# SheetSensor.net
KiCad netlist of a schematic drawn in Altium Designer
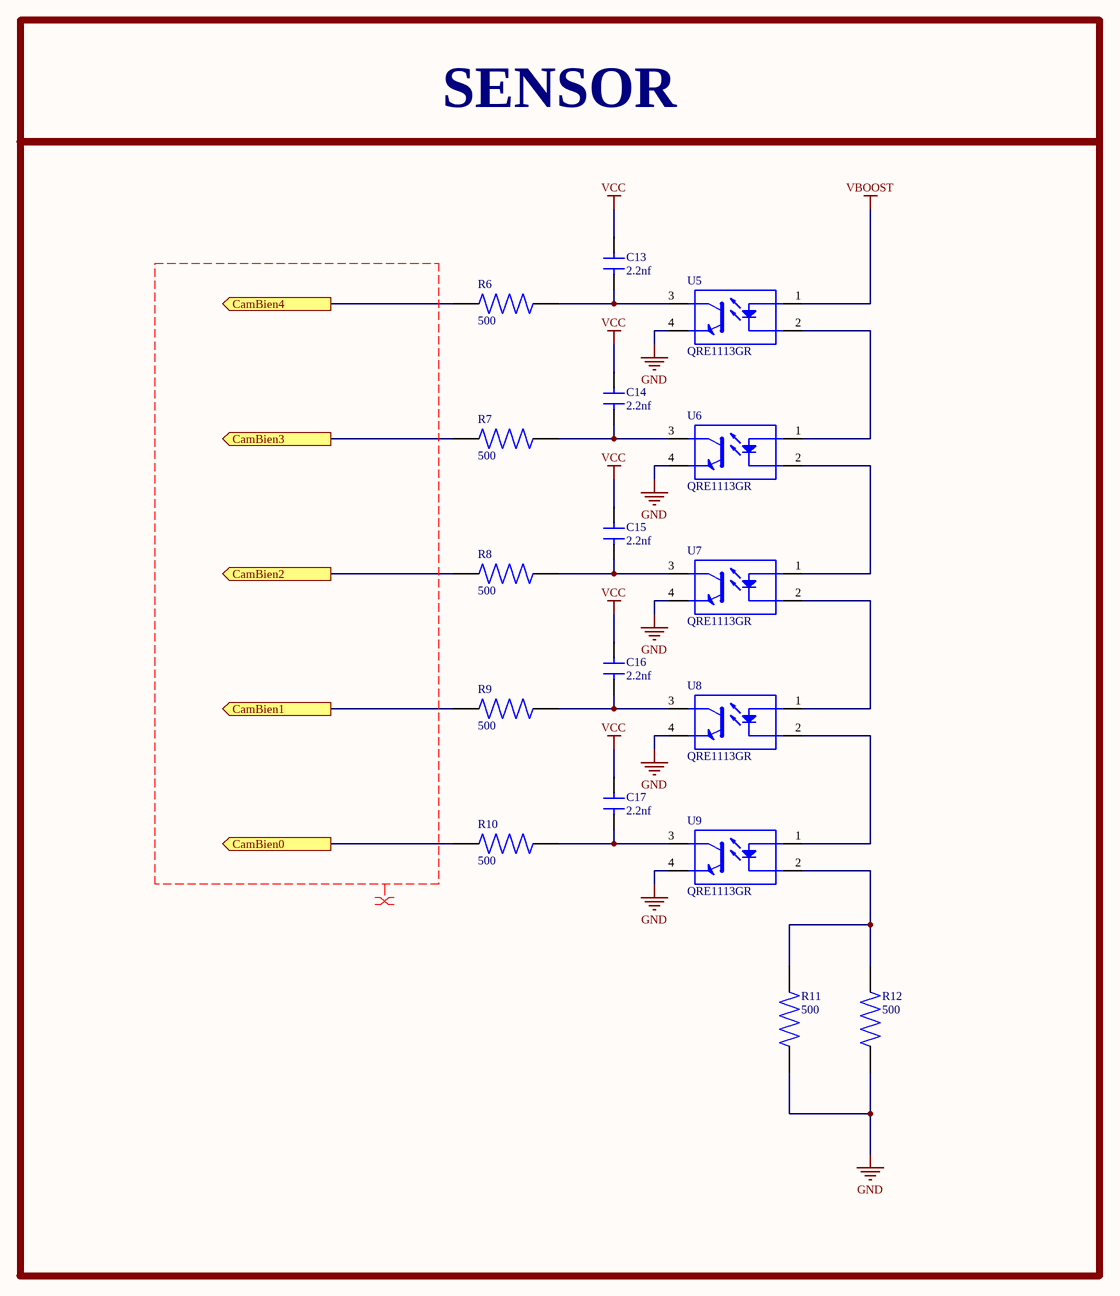
[diagram p0: SheetSensor.SchDoc]

(export (version "E")
  (design (tool "Eeschema 10.0.6"))
  (components
    (comp (ref "C13")
      (value "2.2nf")
      (footprint "C0805 30PF 50V")
      (libsource (lib "SchlibRobotLine") (part "C0805 2.2nf 50v"))
    )
    (comp (ref "C14")
      (value "2.2nf")
      (footprint "C0805 30PF 50V")
      (libsource (lib "SchlibRobotLine") (part "C0805 2.2nf 50v"))
    )
    (comp (ref "C15")
      (value "2.2nf")
      (footprint "C0805 30PF 50V")
      (libsource (lib "SchlibRobotLine") (part "C0805 2.2nf 50v"))
    )
    (comp (ref "C16")
      (value "2.2nf")
      (footprint "C0805 30PF 50V")
      (libsource (lib "SchlibRobotLine") (part "C0805 2.2nf 50v"))
    )
    (comp (ref "C17")
      (value "2.2nf")
      (footprint "C0805 30PF 50V")
      (libsource (lib "SchlibRobotLine") (part "C0805 2.2nf 50v"))
    )
    (comp (ref "R6")
      (value "500")
      (footprint "C0805R500")
      (description "RES SMD 500 OHM 0.05% 1/4W 0805")
      (fields
        (field (name "MANUFACTURER") "Vishay Dale Thin Film")
        (field (name "MANUFACTURER PART NUMBER") "PLT0805Z5000AST5")
      )
      (libsource (lib "SchlibRobotLine") (part "PLT0805Z5000AST5"))
    )
    (comp (ref "R7")
      (value "500")
      (footprint "C0805R500")
      (description "RES SMD 500 OHM 0.05% 1/4W 0805")
      (fields
        (field (name "MANUFACTURER") "Vishay Dale Thin Film")
        (field (name "MANUFACTURER PART NUMBER") "PLT0805Z5000AST5")
      )
      (libsource (lib "SchlibRobotLine") (part "PLT0805Z5000AST5"))
    )
    (comp (ref "R8")
      (value "500")
      (footprint "C0805R500")
      (description "RES SMD 500 OHM 0.05% 1/4W 0805")
      (fields
        (field (name "MANUFACTURER") "Vishay Dale Thin Film")
        (field (name "MANUFACTURER PART NUMBER") "PLT0805Z5000AST5")
      )
      (libsource (lib "SchlibRobotLine") (part "PLT0805Z5000AST5"))
    )
    (comp (ref "R9")
      (value "500")
      (footprint "C0805R500")
      (description "RES SMD 500 OHM 0.05% 1/4W 0805")
      (fields
        (field (name "MANUFACTURER") "Vishay Dale Thin Film")
        (field (name "MANUFACTURER PART NUMBER") "PLT0805Z5000AST5")
      )
      (libsource (lib "SchlibRobotLine") (part "PLT0805Z5000AST5"))
    )
    (comp (ref "R10")
      (value "500")
      (footprint "C0805R500")
      (description "RES SMD 500 OHM 0.05% 1/4W 0805")
      (fields
        (field (name "MANUFACTURER") "Vishay Dale Thin Film")
        (field (name "MANUFACTURER PART NUMBER") "PLT0805Z5000AST5")
      )
      (libsource (lib "SchlibRobotLine") (part "PLT0805Z5000AST5"))
    )
    (comp (ref "R11")
      (value "500")
      (footprint "C0805R500")
      (description "RES SMD 500 OHM 0.05% 1/4W 0805")
      (fields
        (field (name "MANUFACTURER") "Vishay Dale Thin Film")
        (field (name "MANUFACTURER PART NUMBER") "PLT0805Z5000AST5")
      )
      (libsource (lib "SchlibRobotLine") (part "PLT0805Z5000AST5"))
    )
    (comp (ref "R12")
      (value "500")
      (footprint "C0805R500")
      (description "RES SMD 500 OHM 0.05% 1/4W 0805")
      (fields
        (field (name "MANUFACTURER") "Vishay Dale Thin Film")
        (field (name "MANUFACTURER PART NUMBER") "PLT0805Z5000AST5")
      )
      (libsource (lib "SchlibRobotLine") (part "PLT0805Z5000AST5"))
    )
    (comp (ref "U5")
      (value "QRE1113GR")
      (footprint "SOIC180P460X187-4N")
      (description "Photointerrupter Reflective Phototransistor 4-Pin Miniature SMT T/R")
      (fields (field (name "MANUFACTURER") "ON Semiconductor / Fairchild"))
      (libsource (lib "SchlibRobotLine") (part "QRE1113GR"))
    )
    (comp (ref "U6")
      (value "QRE1113GR")
      (footprint "SOIC180P460X187-4N")
      (description "Photointerrupter Reflective Phototransistor 4-Pin Miniature SMT T/R")
      (fields (field (name "MANUFACTURER") "ON Semiconductor / Fairchild"))
      (libsource (lib "SchlibRobotLine") (part "QRE1113GR"))
    )
    (comp (ref "U7")
      (value "QRE1113GR")
      (footprint "SOIC180P460X187-4N")
      (description "Photointerrupter Reflective Phototransistor 4-Pin Miniature SMT T/R")
      (fields (field (name "MANUFACTURER") "ON Semiconductor / Fairchild"))
      (libsource (lib "SchlibRobotLine") (part "QRE1113GR"))
    )
    (comp (ref "U8")
      (value "QRE1113GR")
      (footprint "SOIC180P460X187-4N")
      (description "Photointerrupter Reflective Phototransistor 4-Pin Miniature SMT T/R")
      (fields (field (name "MANUFACTURER") "ON Semiconductor / Fairchild"))
      (libsource (lib "SchlibRobotLine") (part "QRE1113GR"))
    )
    (comp (ref "U9")
      (value "QRE1113GR")
      (footprint "SOIC180P460X187-4N")
      (description "Photointerrupter Reflective Phototransistor 4-Pin Miniature SMT T/R")
      (fields (field (name "MANUFACTURER") "ON Semiconductor / Fairchild"))
      (libsource (lib "SchlibRobotLine") (part "QRE1113GR"))
    )
  )
  (nets
    (net (code "1") (name "/CamBien0") (class "Default")
      (node (ref "R10") (pin "1") (pinfunction "1_1") (pintype "passive"))
    )
    (net (code "2") (name "/CamBien1") (class "Default")
      (node (ref "R9") (pin "1") (pinfunction "1_1") (pintype "passive"))
    )
    (net (code "3") (name "/CamBien2") (class "Default")
      (node (ref "R8") (pin "1") (pinfunction "1_1") (pintype "passive"))
    )
    (net (code "4") (name "/CamBien3") (class "Default")
      (node (ref "R7") (pin "1") (pinfunction "1_1") (pintype "passive"))
    )
    (net (code "5") (name "/CamBien4") (class "Default")
      (node (ref "R6") (pin "1") (pinfunction "1_1") (pintype "passive"))
    )
    (net (code "6") (name "GND") (class "Default")
      (node (ref "R11") (pin "1") (pinfunction "1_1") (pintype "passive"))
      (node (ref "R12") (pin "1") (pinfunction "1_1") (pintype "passive"))
      (node (ref "U5") (pin "4") (pinfunction "4_4") (pintype "passive"))
      (node (ref "U6") (pin "4") (pinfunction "4_4") (pintype "passive"))
      (node (ref "U7") (pin "4") (pinfunction "4_4") (pintype "passive"))
      (node (ref "U8") (pin "4") (pinfunction "4_4") (pintype "passive"))
      (node (ref "U9") (pin "4") (pinfunction "4_4") (pintype "passive"))
    )
    (net (code "7") (name "Net-(C13-Pad1)") (class "Default")
      (node (ref "C13") (pin "1") (pinfunction "1_1") (pintype "passive"))
      (node (ref "R6") (pin "2") (pinfunction "2_2") (pintype "passive"))
      (node (ref "U5") (pin "3") (pinfunction "3_3") (pintype "passive"))
    )
    (net (code "8") (name "Net-(C14-Pad1)") (class "Default")
      (node (ref "C14") (pin "1") (pinfunction "1_1") (pintype "passive"))
      (node (ref "R7") (pin "2") (pinfunction "2_2") (pintype "passive"))
      (node (ref "U6") (pin "3") (pinfunction "3_3") (pintype "passive"))
    )
    (net (code "9") (name "Net-(C15-Pad1)") (class "Default")
      (node (ref "C15") (pin "1") (pinfunction "1_1") (pintype "passive"))
      (node (ref "R8") (pin "2") (pinfunction "2_2") (pintype "passive"))
      (node (ref "U7") (pin "3") (pinfunction "3_3") (pintype "passive"))
    )
    (net (code "10") (name "Net-(C16-Pad1)") (class "Default")
      (node (ref "C16") (pin "1") (pinfunction "1_1") (pintype "passive"))
      (node (ref "R9") (pin "2") (pinfunction "2_2") (pintype "passive"))
      (node (ref "U8") (pin "3") (pinfunction "3_3") (pintype "passive"))
    )
    (net (code "11") (name "Net-(C17-Pad1)") (class "Default")
      (node (ref "C17") (pin "1") (pinfunction "1_1") (pintype "passive"))
      (node (ref "R10") (pin "2") (pinfunction "2_2") (pintype "passive"))
      (node (ref "U9") (pin "3") (pinfunction "3_3") (pintype "passive"))
    )
    (net (code "12") (name "Net-(R11-Pad2)") (class "Default")
      (node (ref "R11") (pin "2") (pinfunction "2_2") (pintype "passive"))
      (node (ref "R12") (pin "2") (pinfunction "2_2") (pintype "passive"))
      (node (ref "U9") (pin "2") (pinfunction "2_2") (pintype "passive"))
    )
    (net (code "13") (name "Net-(U5-Pad2)") (class "Default")
      (node (ref "U5") (pin "2") (pinfunction "2_2") (pintype "passive"))
      (node (ref "U6") (pin "1") (pinfunction "1_1") (pintype "passive"))
    )
    (net (code "14") (name "Net-(U6-Pad2)") (class "Default")
      (node (ref "U6") (pin "2") (pinfunction "2_2") (pintype "passive"))
      (node (ref "U7") (pin "1") (pinfunction "1_1") (pintype "passive"))
    )
    (net (code "15") (name "Net-(U7-Pad2)") (class "Default")
      (node (ref "U7") (pin "2") (pinfunction "2_2") (pintype "passive"))
      (node (ref "U8") (pin "1") (pinfunction "1_1") (pintype "passive"))
    )
    (net (code "16") (name "Net-(U8-Pad2)") (class "Default")
      (node (ref "U8") (pin "2") (pinfunction "2_2") (pintype "passive"))
      (node (ref "U9") (pin "1") (pinfunction "1_1") (pintype "passive"))
    )
    (net (code "17") (name "VBOOST") (class "Default")
      (node (ref "U5") (pin "1") (pinfunction "1_1") (pintype "passive"))
    )
    (net (code "18") (name "VCC") (class "Default")
      (node (ref "C13") (pin "2") (pinfunction "2_2") (pintype "passive"))
      (node (ref "C14") (pin "2") (pinfunction "2_2") (pintype "passive"))
      (node (ref "C15") (pin "2") (pinfunction "2_2") (pintype "passive"))
      (node (ref "C16") (pin "2") (pinfunction "2_2") (pintype "passive"))
      (node (ref "C17") (pin "2") (pinfunction "2_2") (pintype "passive"))
    )
  )
)
